# PowerOldCaps.net
KiCad netlist of a schematic drawn in Altium Designer
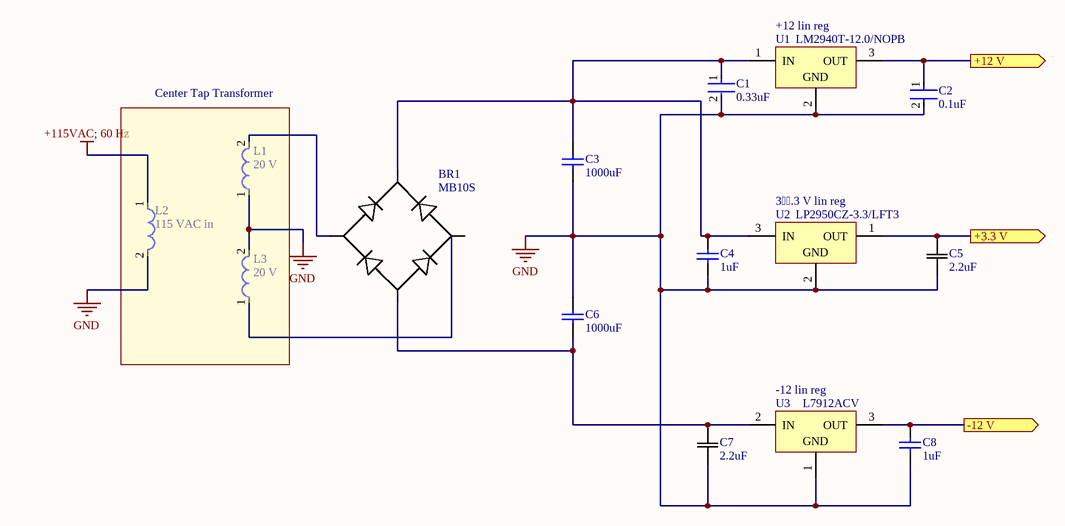
[diagram p0: PowerOldCaps.SchDoc]

(export (version "E")
  (design (tool "Eeschema 10.0.6"))
  (components
    (comp (ref "BR1")
      (value "MB10S")
      (footprint "HDS_DIO")
      (description "No Description Available")
      (fields
        (field (name "MANUFACTURER_PART_NUMBER") "HDS10M-13")
        (field (name "COPYRIGHT") "Copyright (C) 2021 Ultra Librarian. All rights reserved.")
      )
      (libsource (lib "HDS10M-13") (part "HDS10M-13"))
    )
    (comp (ref "C1")
      (value "0.33uF")
      (footprint "FP-C0603C-CF-MFG")
      (description "Cap Ceramic 0.33uF 16V X7R 10% SMD 0603 125°C Punched Paper T/R")
      (fields (field (name "TOLERANCE") "0.1") (field (name "MANUFACTURER PART NUMBER") "C0603C334K4RACAUTO"))
      (libsource (lib "Altium Content Vault") (part "b4654b650e69147ec39a6b967a45e02"))
    )
    (comp (ref "C2")
      (value "0.1uF")
      (footprint "FP-C0603C-CF-MFG")
      (description "CAP CER 0.1UF 50V X7R 0603")
      (fields (field (name "TOLERANCE") "0.1") (field (name "MANUFACTURER") "KEMET"))
      (libsource (lib "Altium Content Vault") (part "b4654b650e69147ec39a6b967a45e02"))
    )
    (comp (ref "C3")
      (value "1000uF")
      (footprint "CAPC3216X110X50LL20T25")
      (description "Chip Capacitor, 1 uF, +/- 10%, 50 V, -55 to 125 degC, 1206 (3216 Metric), RoHS, Tape and Reel")
      (fields (field (name "MANUFACTURER") "Kemet") (field (name "TOLERANCE") "10%"))
      (libsource (lib "Altium Content Vault") (part "CAP-NP-2"))
    )
    (comp (ref "C4")
      (value "1uF")
      (footprint "CAPC3216X110X50LL20T25")
      (description "Chip Capacitor, 1 uF, +/- 10%, 50 V, -55 to 125 degC, 1206 (3216 Metric), RoHS, Tape and Reel")
      (fields (field (name "MANUFACTURER") "Kemet") (field (name "TOLERANCE") "10%"))
      (libsource (lib "Altium Content Vault") (part "CAP-NP-2"))
    )
    (comp (ref "C5")
      (value "2.2uF")
      (footprint "CAPC340180_180N_KEM")
      (description "2.2uF Ceramic cap")
      (fields
        (field (name "MANUFACTURER_PART_NUMBER") "C1206C225K5RACTU")
        (field (name "COPYRIGHT") "Copyright (C) 2021 Ultra Librarian. All rights reserved.")
      )
      (libsource (lib "C1206C225K5RACTU") (part "C1206C225K5RACTU"))
    )
    (comp (ref "C6")
      (value "1000uF")
      (footprint "CAPC3216X110X50LL20T25")
      (description "Chip Capacitor, 1 uF, +/- 10%, 50 V, -55 to 125 degC, 1206 (3216 Metric), RoHS, Tape and Reel")
      (fields (field (name "MANUFACTURER") "Kemet") (field (name "TOLERANCE") "10%"))
      (libsource (lib "Altium Content Vault") (part "CAP-NP-2"))
    )
    (comp (ref "C7")
      (value "2.2uF")
      (footprint "CAPC340180_180N_KEM")
      (description "2.2uF Ceramic cap")
      (fields
        (field (name "MANUFACTURER_PART_NUMBER") "C1206C225K5RACTU")
        (field (name "COPYRIGHT") "Copyright (C) 2021 Ultra Librarian. All rights reserved.")
      )
      (libsource (lib "C1206C225K5RACTU") (part "C1206C225K5RACTU"))
    )
    (comp (ref "C8")
      (value "1uF")
      (footprint "CAPC3216X110X50LL20T25")
      (description "Chip Capacitor, 1 uF, +/- 10%, 50 V, -55 to 125 degC, 1206 (3216 Metric), RoHS, Tape and Reel")
      (fields (field (name "MANUFACTURER") "Kemet") (field (name "TOLERANCE") "10%"))
      (libsource (lib "Altium Content Vault") (part "CAP-NP-2"))
    )
    (comp (ref "L1")
      (value "20 V")
      (footprint "FP-LQH55DN_03-MFG")
      (description "Wire Wound Ferrite Inductor for Power Lines 220μH ±20% 3.36Ω  0.32A 2220")
      (fields (field (name "TOLERANCE") "20%"))
      (libsource (lib "Altium Content Vault") (part "725321dda6339637d4d059423bc1c3c"))
    )
    (comp (ref "L2")
      (value "115 VAC in")
      (footprint "FP-LQH55DN_03-MFG")
      (description "Wire Wound Ferrite Inductor for Power Lines 220μH ±20% 3.36Ω  0.32A 2220")
      (fields (field (name "TOLERANCE") "20%"))
      (libsource (lib "Altium Content Vault") (part "725321dda6339637d4d059423bc1c3c"))
    )
    (comp (ref "L3")
      (value "20 V")
      (footprint "FP-LQH55DN_03-MFG")
      (description "Wire Wound Ferrite Inductor for Power Lines 220μH ±20% 3.36Ω  0.32A 2220")
      (fields (field (name "TOLERANCE") "20%"))
      (libsource (lib "Altium Content Vault") (part "725321dda6339637d4d059423bc1c3c"))
    )
    (comp (ref "U1")
      (value "LM2940T-12.0/NOPB")
      (footprint "NDE0003A")
      (description "1A Low Dropout Regulator, 3-pin TO-220, Pb-Free")
      (fields (field (name "MANUFACTURER") "Texas Instruments"))
      (libsource (lib "Altium Content Vault") (part "PM-REG-LM2940-SIL3"))
    )
    (comp (ref "U2")
      (value "LP2950CZ-3.3/LFT3")
      (footprint "LP0003A")
      (description "Series of Adjustable Micropower Voltage Regulators, 3-pin TO-92, Pb-Free")
      (fields (field (name "MANUFACTURER") "Texas Instruments"))
      (libsource (lib "Altium Content Vault") (part "PM-REG-LM78L05-SIL3"))
    )
    (comp (ref "U3")
      (value "L7912ACV")
      (footprint "TO220")
      (description "2% Negative Voltage Regulator, -12V, 3-Pin TO-220")
      (libsource (lib "Altium Content Vault") (part "PM-REG-7905-SIL3"))
    )
  )
  (nets
    (net (code "1") (name "+115VAC; 60 Hz") (class "Default")
      (node (ref "L2") (pin "1") (pinfunction "1_1") (pintype "passive"))
    )
    (net (code "2") (name "/+3.3 V") (class "Default")
      (node (ref "C5") (pin "2") (pinfunction "2_2") (pintype "passive"))
      (node (ref "U2") (pin "1") (pinfunction "OUT_1") (pintype "power_in"))
    )
    (net (code "3") (name "/+12 V") (class "Default")
      (node (ref "C2") (pin "1") (pinfunction "1_1") (pintype "passive"))
      (node (ref "U1") (pin "3") (pinfunction "OUT_3") (pintype "power_in"))
    )
    (net (code "4") (name "/-12 V") (class "Default")
      (node (ref "C8") (pin "2") (pinfunction "2_2") (pintype "passive"))
      (node (ref "U3") (pin "3") (pinfunction "OUT_3") (pintype "power_in"))
    )
    (net (code "5") (name "GND") (class "Default")
      (node (ref "C1") (pin "2") (pinfunction "2_2") (pintype "passive"))
      (node (ref "C2") (pin "2") (pinfunction "2_2") (pintype "passive"))
      (node (ref "C3") (pin "1") (pinfunction "1_1") (pintype "passive"))
      (node (ref "C4") (pin "1") (pinfunction "1_1") (pintype "passive"))
      (node (ref "C5") (pin "1") (pinfunction "1_1") (pintype "passive"))
      (node (ref "C6") (pin "2") (pinfunction "2_2") (pintype "passive"))
      (node (ref "C7") (pin "1") (pinfunction "1_1") (pintype "passive"))
      (node (ref "C8") (pin "1") (pinfunction "1_1") (pintype "passive"))
      (node (ref "L1") (pin "1") (pinfunction "1_1") (pintype "passive"))
      (node (ref "L2") (pin "2") (pinfunction "2_2") (pintype "passive"))
      (node (ref "L3") (pin "2") (pinfunction "2_2") (pintype "passive"))
      (node (ref "U1") (pin "2") (pinfunction "GND_2") (pintype "power_in"))
      (node (ref "U2") (pin "2") (pinfunction "GND_2") (pintype "power_in"))
      (node (ref "U3") (pin "1") (pinfunction "GND_1") (pintype "power_in"))
    )
    (net (code "6") (name "Net-(BR1-Pad2)") (class "Default")
      (node (ref "BR1") (pin "2") (pinfunction "2_2") (pintype "passive"))
      (node (ref "L1") (pin "2") (pinfunction "2_2") (pintype "passive"))
    )
    (net (code "7") (name "Net-(U1-IN)") (class "Default")
      (node (ref "BR1") (pin "1") (pinfunction "1_1") (pintype "passive"))
      (node (ref "C1") (pin "1") (pinfunction "1_1") (pintype "passive"))
      (node (ref "C3") (pin "2") (pinfunction "2_2") (pintype "passive"))
      (node (ref "C4") (pin "2") (pinfunction "2_2") (pintype "passive"))
      (node (ref "U1") (pin "1") (pinfunction "IN_1") (pintype "power_in"))
      (node (ref "U2") (pin "3") (pinfunction "IN_3") (pintype "power_in"))
    )
    (net (code "8") (name "Net-(U3-IN)") (class "Default")
      (node (ref "BR1") (pin "3") (pinfunction "3_3") (pintype "passive"))
      (node (ref "C6") (pin "1") (pinfunction "1_1") (pintype "passive"))
      (node (ref "C7") (pin "2") (pinfunction "2_2") (pintype "passive"))
      (node (ref "U3") (pin "2") (pinfunction "IN_2") (pintype "power_in"))
    )
    (net (code "9") (name "unconnected-(BR1-Pad4)") (class "Default")
      (node (ref "BR1") (pin "4") (pinfunction "4_4") (pintype "passive"))
    )
    (net (code "10") (name "unconnected-(L3-Pad1)") (class "Default")
      (node (ref "L3") (pin "1") (pinfunction "1_1") (pintype "passive"))
    )
  )
)
